# rgb.net
KiCad netlist of a schematic drawn in EAGLE
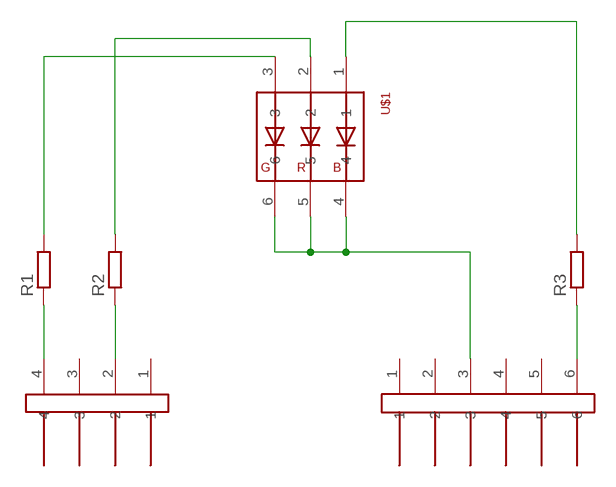
[diagram p0: schematic, sheet 1]

(export (version "E")
  (design (tool "Eeschema 10.0.6"))
  (components
    (comp (ref "R1")
      (value "R-EU_R0603")
      (footprint "eagle-import:R0603")
      (libsource (lib "eagle-import") (part "R-EU_R0603"))
    )
    (comp (ref "R2")
      (value "R-EU_R0603")
      (footprint "eagle-import:R0603")
      (libsource (lib "eagle-import") (part "R-EU_R0603"))
    )
    (comp (ref "R3")
      (value "R-EU_R0603")
      (footprint "eagle-import:R0603")
      (libsource (lib "eagle-import") (part "R-EU_R0603"))
    )
    (comp (ref "U$1")
      (value "RGB_WW-FCE50TC-Q1")
      (footprint "eagle-import:RGB_WW-FCE50TC-Q1")
      (libsource (lib "eagle-import") (part "RGB_WW-FCE50TC-Q1"))
    )
    (comp (ref "U$8")
      (value "JUMPER6M")
      (footprint "eagle-import:JUMPER6M")
      (libsource (lib "eagle-import") (part "JUMPER6M"))
    )
    (comp (ref "U$9")
      (value "JUMPER4M")
      (footprint "eagle-import:JUMPER4M")
      (libsource (lib "eagle-import") (part "JUMPER4M"))
    )
  )
  (nets
    (net (code "1") (name "Net-(R1-Pad1)") (class "Default")
      (node (ref "R1") (pin "1") (pinfunction "1_1") (pintype "passive"))
      (node (ref "U$9") (pin "4") (pinfunction "4_4") (pintype "bidirectional"))
    )
    (net (code "2") (name "Net-(R1-Pad2)") (class "Default")
      (node (ref "R1") (pin "2") (pinfunction "2_2") (pintype "passive"))
      (node (ref "U$1") (pin "3") (pinfunction "3_3") (pintype "bidirectional"))
    )
    (net (code "3") (name "Net-(R2-Pad1)") (class "Default")
      (node (ref "R2") (pin "1") (pinfunction "1_1") (pintype "passive"))
      (node (ref "U$9") (pin "2") (pinfunction "2_2") (pintype "bidirectional"))
    )
    (net (code "4") (name "Net-(R2-Pad2)") (class "Default")
      (node (ref "R2") (pin "2") (pinfunction "2_2") (pintype "passive"))
      (node (ref "U$1") (pin "2") (pinfunction "2_2") (pintype "bidirectional"))
    )
    (net (code "5") (name "Net-(R3-Pad1)") (class "Default")
      (node (ref "R3") (pin "1") (pinfunction "1_1") (pintype "passive"))
      (node (ref "U$8") (pin "6") (pinfunction "6_6") (pintype "bidirectional"))
    )
    (net (code "6") (name "Net-(R3-Pad2)") (class "Default")
      (node (ref "R3") (pin "2") (pinfunction "2_2") (pintype "passive"))
      (node (ref "U$1") (pin "1") (pinfunction "1_1") (pintype "bidirectional"))
    )
    (net (code "7") (name "Net-(U$1-Pad4)") (class "Default")
      (node (ref "U$1") (pin "4") (pinfunction "4_4") (pintype "bidirectional"))
      (node (ref "U$1") (pin "5") (pinfunction "5_5") (pintype "bidirectional"))
      (node (ref "U$1") (pin "6") (pinfunction "6_6") (pintype "bidirectional"))
      (node (ref "U$8") (pin "3") (pinfunction "3_3") (pintype "bidirectional"))
    )
    (net (code "8") (name "unconnected-(U$8-Pad1)") (class "Default")
      (node (ref "U$8") (pin "1") (pinfunction "1_1") (pintype "bidirectional"))
    )
    (net (code "9") (name "unconnected-(U$8-Pad2)") (class "Default")
      (node (ref "U$8") (pin "2") (pinfunction "2_2") (pintype "bidirectional"))
    )
    (net (code "10") (name "unconnected-(U$8-Pad4)") (class "Default")
      (node (ref "U$8") (pin "4") (pinfunction "4_4") (pintype "bidirectional"))
    )
    (net (code "11") (name "unconnected-(U$8-Pad5)") (class "Default")
      (node (ref "U$8") (pin "5") (pinfunction "5_5") (pintype "bidirectional"))
    )
    (net (code "12") (name "unconnected-(U$9-Pad1)") (class "Default")
      (node (ref "U$9") (pin "1") (pinfunction "1_1") (pintype "bidirectional"))
    )
    (net (code "13") (name "unconnected-(U$9-Pad3)") (class "Default")
      (node (ref "U$9") (pin "3") (pinfunction "3_3") (pintype "bidirectional"))
    )
  )
)
